# Power_Supply_for_CPU_Blocks.net
KiCad netlist of a schematic drawn in Altium Designer
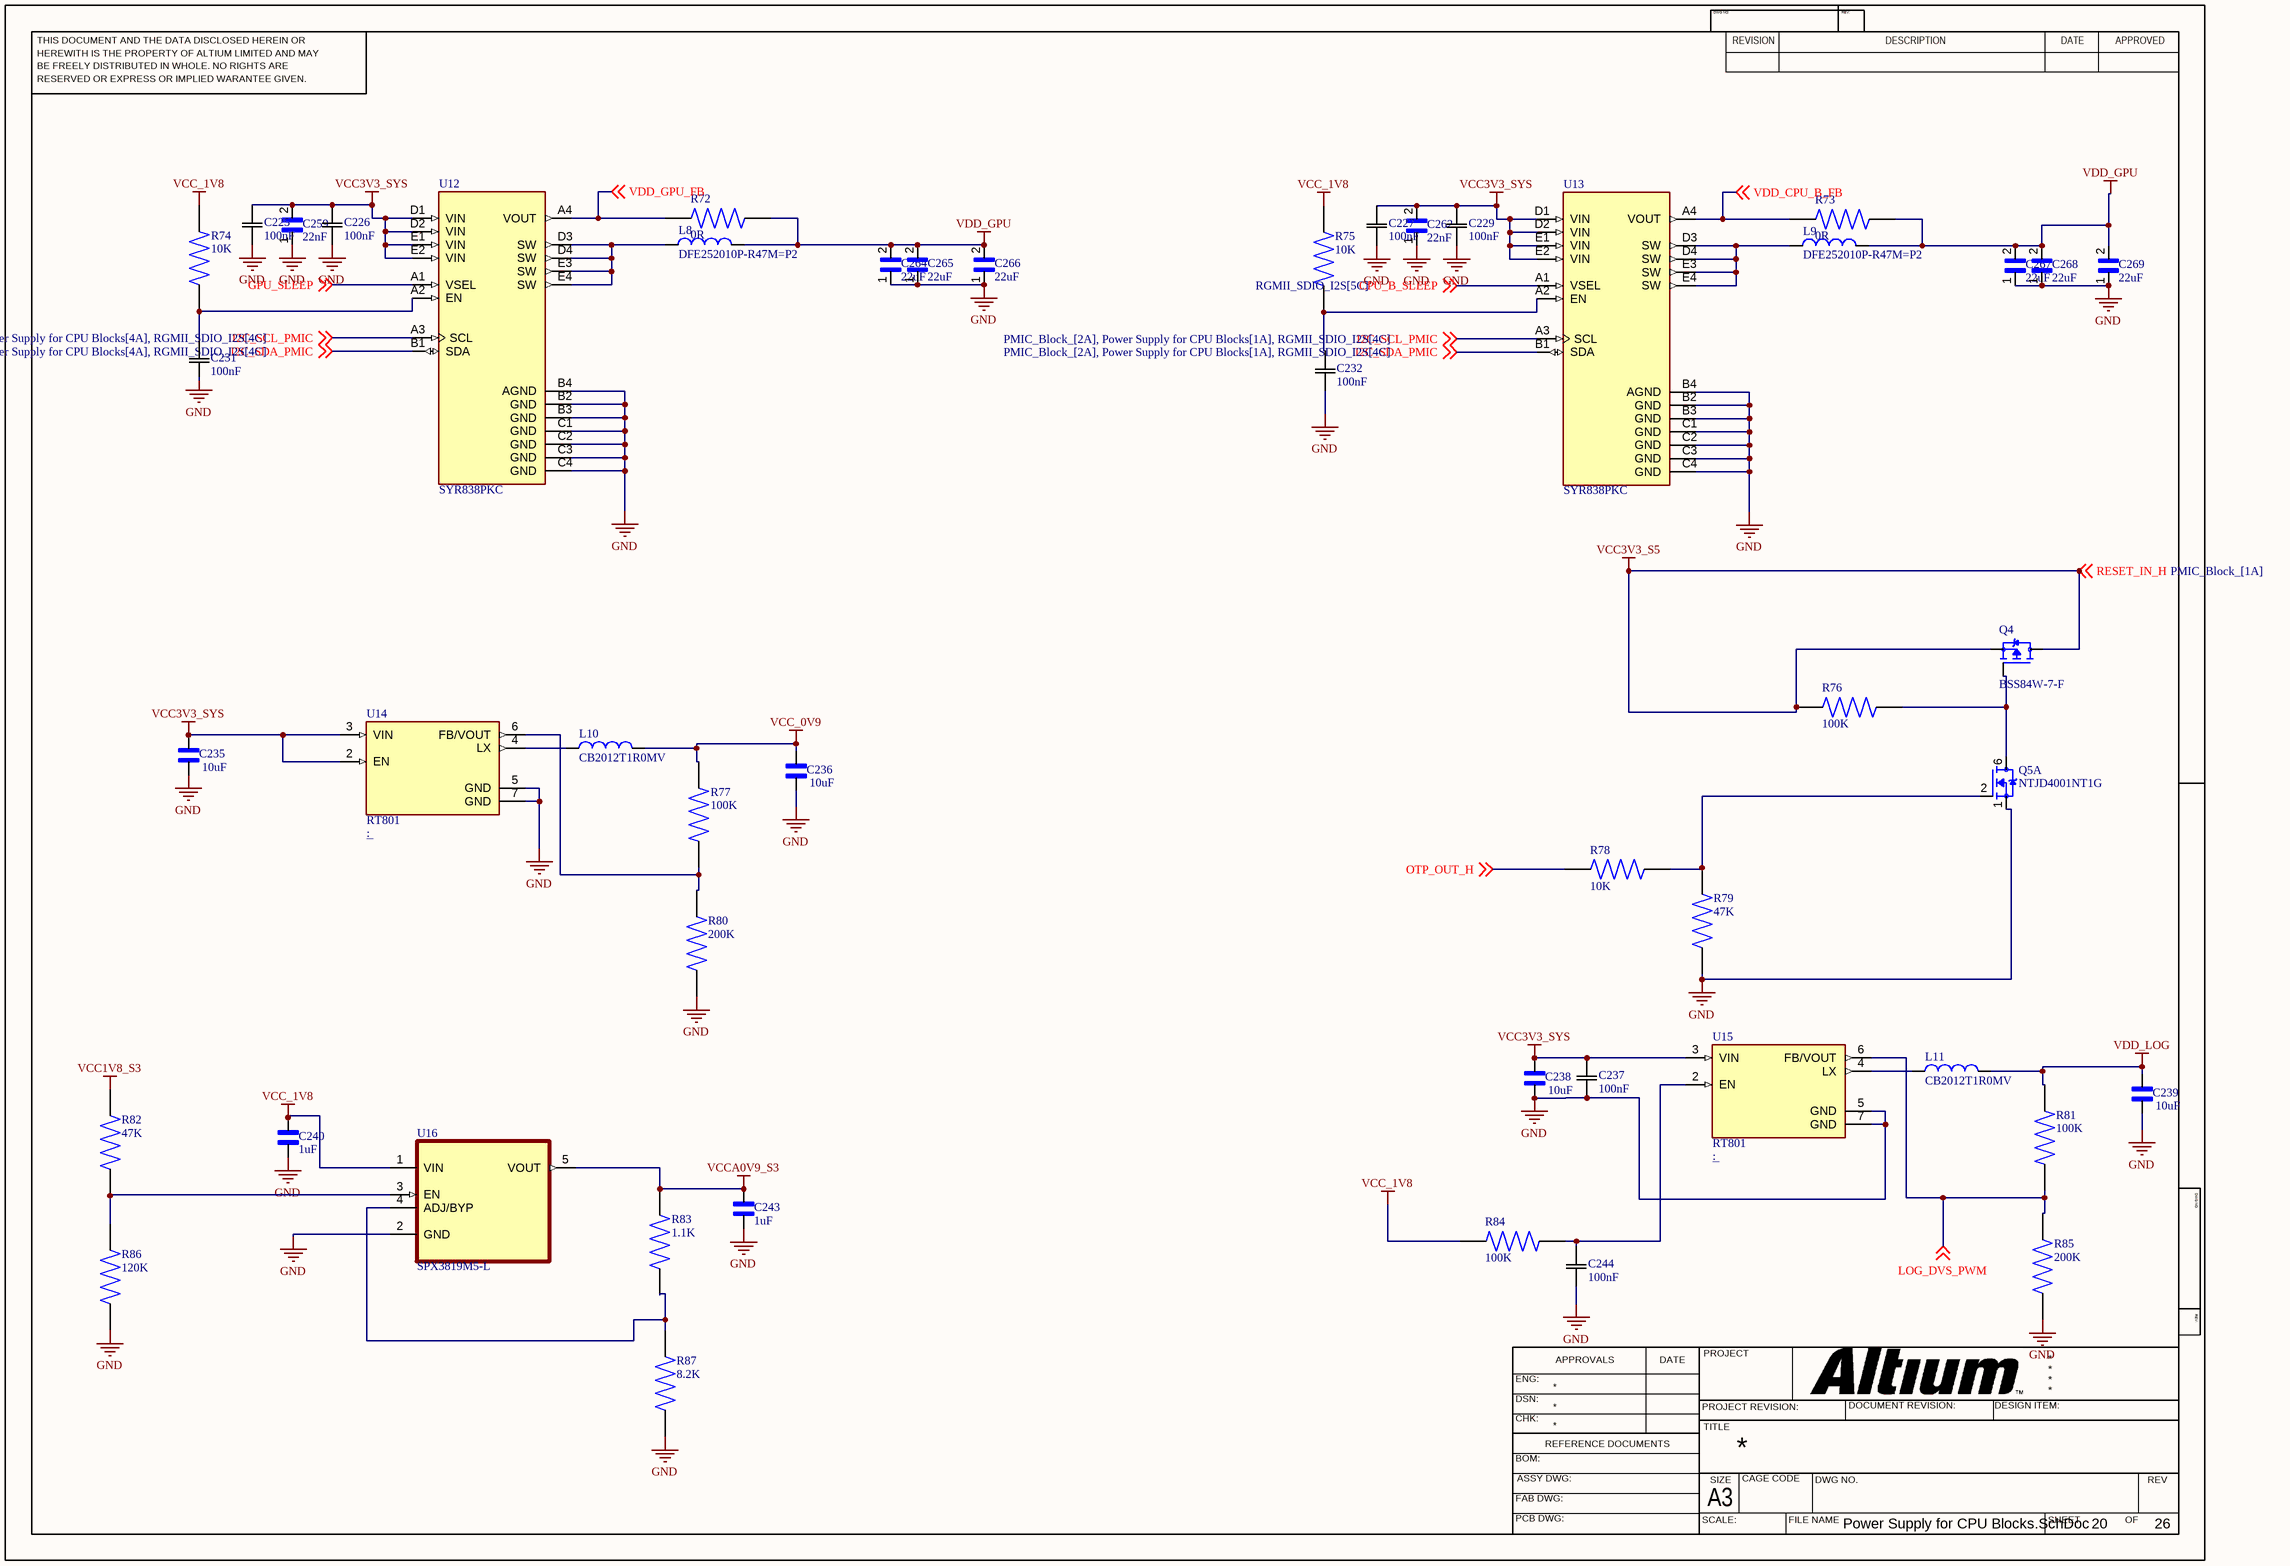
[diagram p0: Power Supply for CPU Blocks.SchDoc]

(export (version "E")
  (design (tool "Eeschema 10.0.6"))
  (components
    (comp (ref "C225")
      (value "100nF")
      (footprint "CAP_1005_TDK")
      (description "Description")
      (fields
        (field (name "MANUFACTURER_PART_NUMBER") "C1005X7R1H104M050BB")
        (field (name "COPYRIGHT") "Copyright (C) 2025 Ultra Librarian. All rights reserved.")
      )
      (libsource (lib "C1005X7R1H104M050BB") (part "C1005X7R1H104M050BB"))
    )
    (comp (ref "C226")
      (value "100nF")
      (footprint "CAP_1005_TDK")
      (description "Description")
      (fields
        (field (name "MANUFACTURER_PART_NUMBER") "C1005X7R1H104M050BB")
        (field (name "COPYRIGHT") "Copyright (C) 2025 Ultra Librarian. All rights reserved.")
      )
      (libsource (lib "C1005X7R1H104M050BB") (part "C1005X7R1H104M050BB"))
    )
    (comp (ref "C227")
      (value "100nF")
      (footprint "CAP_1005_TDK")
      (description "Description")
      (fields
        (field (name "MANUFACTURER_PART_NUMBER") "C1005X7R1H104M050BB")
        (field (name "COPYRIGHT") "Copyright (C) 2025 Ultra Librarian. All rights reserved.")
      )
      (libsource (lib "C1005X7R1H104M050BB") (part "C1005X7R1H104M050BB"))
    )
    (comp (ref "C229")
      (value "100nF")
      (footprint "CAP_1005_TDK")
      (description "Description")
      (fields
        (field (name "MANUFACTURER_PART_NUMBER") "C1005X7R1H104M050BB")
        (field (name "COPYRIGHT") "Copyright (C) 2025 Ultra Librarian. All rights reserved.")
      )
      (libsource (lib "C1005X7R1H104M050BB") (part "C1005X7R1H104M050BB"))
    )
    (comp (ref "C231")
      (value "100nF")
      (footprint "CAP_1005_TDK")
      (description "Description")
      (fields
        (field (name "MANUFACTURER_PART_NUMBER") "C1005X7R1H104M050BB")
        (field (name "COPYRIGHT") "Copyright (C) 2025 Ultra Librarian. All rights reserved.")
      )
      (libsource (lib "C1005X7R1H104M050BB") (part "C1005X7R1H104M050BB"))
    )
    (comp (ref "C232")
      (value "100nF")
      (footprint "CAP_1005_TDK")
      (description "Description")
      (fields
        (field (name "MANUFACTURER_PART_NUMBER") "C1005X7R1H104M050BB")
        (field (name "COPYRIGHT") "Copyright (C) 2025 Ultra Librarian. All rights reserved.")
      )
      (libsource (lib "C1005X7R1H104M050BB") (part "C1005X7R1H104M050BB"))
    )
    (comp (ref "C235")
      (value "10uF")
      (footprint "CAPC1005X70N")
      (description "10 ÂµF Â±20% 6.3V Ceramic Capacitor X5R 0402 (1005 Metric)")
      (fields (field (name "MF") "Samsung") (field (name "MP") "CL05A106MQ5NUNC"))
      (libsource (lib "CL05A106MQ5NUNC") (part "CL05A106MQ5NUNC"))
    )
    (comp (ref "C236")
      (value "10uF")
      (footprint "CAPC1005X70N")
      (description "10 ÂµF Â±20% 6.3V Ceramic Capacitor X5R 0402 (1005 Metric)")
      (fields (field (name "MF") "Samsung") (field (name "MP") "CL05A106MQ5NUNC"))
      (libsource (lib "CL05A106MQ5NUNC") (part "CL05A106MQ5NUNC"))
    )
    (comp (ref "C237")
      (value "100nF")
      (footprint "CAP_1005_TDK")
      (description "Description")
      (fields
        (field (name "MANUFACTURER_PART_NUMBER") "C1005X7R1H104M050BB")
        (field (name "COPYRIGHT") "Copyright (C) 2025 Ultra Librarian. All rights reserved.")
      )
      (libsource (lib "C1005X7R1H104M050BB") (part "C1005X7R1H104M050BB"))
    )
    (comp (ref "C238")
      (value "10uF")
      (footprint "CAPC1005X70N")
      (description "10 ÂµF Â±20% 6.3V Ceramic Capacitor X5R 0402 (1005 Metric)")
      (fields (field (name "MF") "Samsung") (field (name "MP") "CL05A106MQ5NUNC"))
      (libsource (lib "CL05A106MQ5NUNC") (part "CL05A106MQ5NUNC"))
    )
    (comp (ref "C239")
      (value "10uF")
      (footprint "CAPC1005X70N")
      (description "10 ÂµF Â±20% 6.3V Ceramic Capacitor X5R 0402 (1005 Metric)")
      (fields (field (name "MF") "Samsung") (field (name "MP") "CL05A106MQ5NUNC"))
      (libsource (lib "CL05A106MQ5NUNC") (part "CL05A106MQ5NUNC"))
    )
    (comp (ref "C240")
      (value "1uF")
      (footprint "CAPC1005X56N")
      (description "1 ÂµF Â±10% 10V Ceramic Capacitor X5R 0402 (1005 Metric)")
      (fields (field (name "MF") "AVX") (field (name "MP") "0402ZD105KAT4A"))
      (libsource (lib "0402ZD105KAT4A") (part "0402ZD105KAT4A"))
    )
    (comp (ref "C243")
      (value "1uF")
      (footprint "CAPC1005X56N")
      (description "1 ÂµF Â±10% 10V Ceramic Capacitor X5R 0402 (1005 Metric)")
      (fields (field (name "MF") "AVX") (field (name "MP") "0402ZD105KAT4A"))
      (libsource (lib "0402ZD105KAT4A") (part "0402ZD105KAT4A"))
    )
    (comp (ref "C244")
      (value "100nF")
      (footprint "CAP_1005_TDK")
      (description "Description")
      (fields
        (field (name "MANUFACTURER_PART_NUMBER") "C1005X7R1H104M050BB")
        (field (name "COPYRIGHT") "Copyright (C) 2025 Ultra Librarian. All rights reserved.")
      )
      (libsource (lib "C1005X7R1H104M050BB") (part "C1005X7R1H104M050BB"))
    )
    (comp (ref "C259")
      (value "22nF")
      (footprint "CAPC6050X550N")
      (description "22ÂµF Â±20% 50V Ceramic Capacitor X7S Stacked SMD, 2 J-Lead")
      (fields (field (name "MP") "CKG57NX7S1H226M500JJ"))
      (libsource (lib "CKG57NX7S1H226M500JJ") (part "CKG57NX7S1H226M500JJ"))
    )
    (comp (ref "C262")
      (value "22nF")
      (footprint "CAPC6050X550N")
      (description "22ÂµF Â±20% 50V Ceramic Capacitor X7S Stacked SMD, 2 J-Lead")
      (fields (field (name "MP") "CKG57NX7S1H226M500JJ"))
      (libsource (lib "CKG57NX7S1H226M500JJ") (part "CKG57NX7S1H226M500JJ"))
    )
    (comp (ref "C264")
      (value "22uF")
      (footprint "CAPC6050X550N")
      (description "22ÂµF Â±20% 50V Ceramic Capacitor X7S Stacked SMD, 2 J-Lead")
      (fields (field (name "MP") "CKG57NX7S1H226M500JJ"))
      (libsource (lib "CKG57NX7S1H226M500JJ") (part "CKG57NX7S1H226M500JJ"))
    )
    (comp (ref "C265")
      (value "22uF")
      (footprint "CAPC6050X550N")
      (description "22ÂµF Â±20% 50V Ceramic Capacitor X7S Stacked SMD, 2 J-Lead")
      (fields (field (name "MP") "CKG57NX7S1H226M500JJ"))
      (libsource (lib "CKG57NX7S1H226M500JJ") (part "CKG57NX7S1H226M500JJ"))
    )
    (comp (ref "C266")
      (value "22uF")
      (footprint "CAPC6050X550N")
      (description "22ÂµF Â±20% 50V Ceramic Capacitor X7S Stacked SMD, 2 J-Lead")
      (fields (field (name "MP") "CKG57NX7S1H226M500JJ"))
      (libsource (lib "CKG57NX7S1H226M500JJ") (part "CKG57NX7S1H226M500JJ"))
    )
    (comp (ref "C267")
      (value "22uF")
      (footprint "CAPC6050X550N")
      (description "22ÂµF Â±20% 50V Ceramic Capacitor X7S Stacked SMD, 2 J-Lead")
      (fields (field (name "MP") "CKG57NX7S1H226M500JJ"))
      (libsource (lib "CKG57NX7S1H226M500JJ") (part "CKG57NX7S1H226M500JJ"))
    )
    (comp (ref "C268")
      (value "22uF")
      (footprint "CAPC6050X550N")
      (description "22ÂµF Â±20% 50V Ceramic Capacitor X7S Stacked SMD, 2 J-Lead")
      (fields (field (name "MP") "CKG57NX7S1H226M500JJ"))
      (libsource (lib "CKG57NX7S1H226M500JJ") (part "CKG57NX7S1H226M500JJ"))
    )
    (comp (ref "C269")
      (value "22uF")
      (footprint "CAPC6050X550N")
      (description "22ÂµF Â±20% 50V Ceramic Capacitor X7S Stacked SMD, 2 J-Lead")
      (fields (field (name "MP") "CKG57NX7S1H226M500JJ"))
      (libsource (lib "CKG57NX7S1H226M500JJ") (part "CKG57NX7S1H226M500JJ"))
    )
    (comp (ref "L8")
      (value "DFE252010P-R47M=P2")
      (footprint "INDC2520X100N")
      (description "INDUCTOR, SHLD, 0.47UH, 20%, 4.1A, 1008")
      (libsource (lib "DFE252010P-R47M=P2") (part "DFE252010P-R47M=P2"))
    )
    (comp (ref "L9")
      (value "DFE252010P-R47M=P2")
      (footprint "INDC2520X100N")
      (description "INDUCTOR, SHLD, 0.47UH, 20%, 4.1A, 1008")
      (libsource (lib "DFE252010P-R47M=P2") (part "DFE252010P-R47M=P2"))
    )
    (comp (ref "L10")
      (value "CB2012T1R0MV")
      (footprint "INDC2012X145N")
      (description "1 ÂµH Unshielded Drum Core, Wirewound Inductor 700 mA 195mOhm Max 0805 (2012 Metric)")
      (fields (field (name "MF") "Taiyo Yuden"))
      (libsource (lib "CB2012T1R0MV") (part "CB2012T1R0MV"))
    )
    (comp (ref "L11")
      (value "CB2012T1R0MV")
      (footprint "INDC2012X145N")
      (description "1 ÂµH Unshielded Drum Core, Wirewound Inductor 700 mA 195mOhm Max 0805 (2012 Metric)")
      (fields (field (name "MF") "Taiyo Yuden"))
      (libsource (lib "CB2012T1R0MV") (part "CB2012T1R0MV"))
    )
    (comp (ref "Q4")
      (value "BSS84W-7-F")
      (footprint "SOT65P222X110-3N")
      (description "P-Channel 50 V 130mA (Ta) 200mW (Ta) Surface Mount SOT-323")
      (fields (field (name "MF") "Diodes Inc."))
      (libsource (lib "BSS84W-7-F") (part "BSS84W-7-F"))
    )
    (comp (ref "Q5")
      (value "NTJD4001NT1G")
      (footprint "SOT65P210X110-6N")
      (description "Mosfet Array 2 N-Channel (Dual) 30V 250mA 272mW Surface Mount SC-88/SC70-6/SOT-363")
      (fields (field (name "MF") "ON Semiconductor"))
      (libsource (lib "NTJD4001NT1G") (part "NTJD4001NT1G"))
    )
    (comp (ref "R72")
      (value "0R")
      (footprint "RES_ERJH6G0R00V")
      (fields (field (name "MP") "ERJH6G0R00V"))
      (libsource (lib "ERJH6G0R00V") (part "ERJH6G0R00V"))
    )
    (comp (ref "R73")
      (value "0R")
      (footprint "RES_ERJH6G0R00V")
      (fields (field (name "MP") "ERJH6G0R00V"))
      (libsource (lib "ERJH6G0R00V") (part "ERJH6G0R00V"))
    )
    (comp (ref "R74")
      (value "10K")
      (footprint "RES_ERA3ARB103V")
      (fields (field (name "MP") "ERA3ARB103V"))
      (libsource (lib "ERA3ARB103V") (part "ERA3ARB103V"))
    )
    (comp (ref "R75")
      (value "10K")
      (footprint "RES_ERA3ARB103V")
      (fields (field (name "MP") "ERA3ARB103V"))
      (libsource (lib "ERA3ARB103V") (part "ERA3ARB103V"))
    )
    (comp (ref "R76")
      (value "100K")
      (footprint "RES_ERA3ARB103V")
      (fields (field (name "MP") "ERA3ARB103V"))
      (libsource (lib "ERA3ARB103V") (part "ERA3ARB103V"))
    )
    (comp (ref "R77")
      (value "100K")
      (footprint "RES_ERA3ARB103V")
      (fields (field (name "MP") "ERA3ARB103V"))
      (libsource (lib "ERA3ARB103V") (part "ERA3ARB103V"))
    )
    (comp (ref "R78")
      (value "10K")
      (footprint "RES_ERA3ARB103V")
      (fields (field (name "MP") "ERA3ARB103V"))
      (libsource (lib "ERA3ARB103V") (part "ERA3ARB103V"))
    )
    (comp (ref "R79")
      (value "47K")
      (footprint "RES_ERA2ARC473X")
      (fields (field (name "MP") "ERA2ARC473X"))
      (libsource (lib "ERA2ARC473X") (part "ERA2ARC473X"))
    )
    (comp (ref "R80")
      (value "200K")
      (footprint "RES_ERJP06D2003V")
      (fields (field (name "MP") "ERJP06D2003V"))
      (libsource (lib "ERJP06D2003V") (part "ERJP06D2003V"))
    )
    (comp (ref "R81")
      (value "100K")
      (footprint "RES_ERA3ARB103V")
      (fields (field (name "MP") "ERA3ARB103V"))
      (libsource (lib "ERA3ARB103V") (part "ERA3ARB103V"))
    )
    (comp (ref "R82")
      (value "47K")
      (footprint "RES_ERA2ARC473X")
      (fields (field (name "MP") "ERA2ARC473X"))
      (libsource (lib "ERA2ARC473X") (part "ERA2ARC473X"))
    )
    (comp (ref "R83")
      (value "1.1K")
      (footprint "RESC1608X50N")
      (fields (field (name "MP") "ERJP08F1101V"))
      (libsource (lib "ERJP08F1101V") (part "ERJP08F1101V"))
    )
    (comp (ref "R84")
      (value "100K")
      (footprint "RES_ERA3ARB103V")
      (fields (field (name "MP") "ERA3ARB103V"))
      (libsource (lib "ERA3ARB103V") (part "ERA3ARB103V"))
    )
    (comp (ref "R85")
      (value "200K")
      (footprint "RES_ERJP06D2003V")
      (fields (field (name "MP") "ERJP06D2003V"))
      (libsource (lib "ERJP06D2003V") (part "ERJP06D2003V"))
    )
    (comp (ref "R86")
      (value "120K")
      (footprint "RES_ERA8AEB124V")
      (fields (field (name "MP") "ERA8AEB124V"))
      (libsource (lib "ERA8AEB124V") (part "ERA8AEB124V"))
    )
    (comp (ref "R87")
      (value "8.2K")
      (footprint "RES_ERA2APB822X")
      (fields (field (name "MP") "ERA2APB822X"))
      (libsource (lib "ERA2APB822X") (part "ERA2APB822X"))
    )
    (comp (ref "U12")
      (value "SYR838PKC")
      (footprint "BGA20N40P5X4_196X156X66N")
      (fields (field (name "MF") "Silergy"))
      (libsource (lib "SYR838PKC") (part "SYR838PKC"))
    )
    (comp (ref "U13")
      (value "SYR838PKC")
      (footprint "BGA20N40P5X4_196X156X66N")
      (fields (field (name "MF") "Silergy"))
      (libsource (lib "SYR838PKC") (part "SYR838PKC"))
    )
    (comp (ref "U14")
      (value "RT801")
      (footprint "SON65P200X200X80-7N")
      (description "Buck Switching Regulator IC Positive Adjustable 0.6V 1 Output 1A 6-WDFN Exposed Pad")
      (fields (field (name "MP") "RT8010GQW") (field (name "MF") "Richtek USA"))
      (libsource (lib "RT8010GQW") (part "RT8010GQW"))
    )
    (comp (ref "U15")
      (value "RT801")
      (footprint "SON65P200X200X80-7N")
      (description "Buck Switching Regulator IC Positive Adjustable 0.6V 1 Output 1A 6-WDFN Exposed Pad")
      (fields (field (name "MP") "RT8010GQW") (field (name "MF") "Richtek USA"))
      (libsource (lib "RT8010GQW") (part "RT8010GQW"))
    )
    (comp (ref "U16")
      (value "SPX3819M5-L")
      (footprint "SOT95P280X145-5N")
      (description "Linear Voltage Regulator IC Positive Adjustable 1 Output 500mA SOT-23-5")
      (fields (field (name "MF") "MaxLinear, Inc.") (field (name "MP") "SPX3819M5-L/TR"))
      (libsource (lib "SPX3819M5-L") (part "SPX3819M5-L"))
    )
  )
  (nets
    (net (code "1") (name "CPU_B_SLEEP") (class "Default")
      (node (ref "U13") (pin "A1") (pinfunction "VSEL_A1") (pintype "input"))
    )
    (net (code "2") (name "GND") (class "Default")
      (node (ref "C225") (pin "1") (pinfunction "1_1") (pintype "passive"))
      (node (ref "C226") (pin "1") (pinfunction "1_1") (pintype "passive"))
      (node (ref "C227") (pin "1") (pinfunction "1_1") (pintype "passive"))
      (node (ref "C229") (pin "1") (pinfunction "1_1") (pintype "passive"))
      (node (ref "C231") (pin "1") (pinfunction "1_1") (pintype "passive"))
      (node (ref "C232") (pin "1") (pinfunction "1_1") (pintype "passive"))
      (node (ref "C235") (pin "1") (pinfunction "1_1") (pintype "passive"))
      (node (ref "C236") (pin "1") (pinfunction "1_1") (pintype "passive"))
      (node (ref "C237") (pin "1") (pinfunction "1_1") (pintype "passive"))
      (node (ref "C238") (pin "1") (pinfunction "1_1") (pintype "passive"))
      (node (ref "C239") (pin "1") (pinfunction "1_1") (pintype "passive"))
      (node (ref "C240") (pin "1") (pinfunction "1_1") (pintype "passive"))
      (node (ref "C243") (pin "1") (pinfunction "1_1") (pintype "passive"))
      (node (ref "C244") (pin "1") (pinfunction "1_1") (pintype "passive"))
      (node (ref "C259") (pin "1") (pinfunction "1_1") (pintype "passive"))
      (node (ref "C262") (pin "1") (pinfunction "1_1") (pintype "passive"))
      (node (ref "C264") (pin "1") (pinfunction "1_1") (pintype "passive"))
      (node (ref "C265") (pin "1") (pinfunction "1_1") (pintype "passive"))
      (node (ref "C266") (pin "1") (pinfunction "1_1") (pintype "passive"))
      (node (ref "C267") (pin "1") (pinfunction "1_1") (pintype "passive"))
      (node (ref "C268") (pin "1") (pinfunction "1_1") (pintype "passive"))
      (node (ref "C269") (pin "1") (pinfunction "1_1") (pintype "passive"))
      (node (ref "Q5") (pin "1") (pinfunction "S1_1") (pintype "passive"))
      (node (ref "R79") (pin "1") (pinfunction "1_1") (pintype "passive"))
      (node (ref "R80") (pin "1") (pinfunction "1_1") (pintype "passive"))
      (node (ref "R85") (pin "1") (pinfunction "1_1") (pintype "passive"))
      (node (ref "R86") (pin "1") (pinfunction "1_1") (pintype "passive"))
      (node (ref "R87") (pin "1") (pinfunction "1_1") (pintype "passive"))
      (node (ref "U12") (pin "B2") (pinfunction "GND_B2") (pintype "power_in"))
      (node (ref "U12") (pin "B3") (pinfunction "GND_B3") (pintype "power_in"))
      (node (ref "U12") (pin "B4") (pinfunction "AGND_B4") (pintype "power_in"))
      (node (ref "U12") (pin "C1") (pinfunction "GND_C1") (pintype "power_in"))
      (node (ref "U12") (pin "C2") (pinfunction "GND_C2") (pintype "power_in"))
      (node (ref "U12") (pin "C3") (pinfunction "GND_C3") (pintype "power_in"))
      (node (ref "U12") (pin "C4") (pinfunction "GND_C4") (pintype "power_in"))
      (node (ref "U13") (pin "B2") (pinfunction "GND_B2") (pintype "power_in"))
      (node (ref "U13") (pin "B3") (pinfunction "GND_B3") (pintype "power_in"))
      (node (ref "U13") (pin "B4") (pinfunction "AGND_B4") (pintype "power_in"))
      (node (ref "U13") (pin "C1") (pinfunction "GND_C1") (pintype "power_in"))
      (node (ref "U13") (pin "C2") (pinfunction "GND_C2") (pintype "power_in"))
      (node (ref "U13") (pin "C3") (pinfunction "GND_C3") (pintype "power_in"))
      (node (ref "U13") (pin "C4") (pinfunction "GND_C4") (pintype "power_in"))
      (node (ref "U14") (pin "5") (pinfunction "GND_5") (pintype "power_in"))
      (node (ref "U14") (pin "7") (pinfunction "GND_7") (pintype "power_in"))
      (node (ref "U15") (pin "5") (pinfunction "GND_5") (pintype "power_in"))
      (node (ref "U15") (pin "7") (pinfunction "GND_7") (pintype "power_in"))
      (node (ref "U16") (pin "2") (pinfunction "GND_2") (pintype "passive"))
    )
    (net (code "3") (name "GPU_SLEEP") (class "Default")
      (node (ref "U12") (pin "A1") (pinfunction "VSEL_A1") (pintype "input"))
    )
    (net (code "4") (name "I2C_SCL_PMIC") (class "Default")
      (node (ref "U12") (pin "A3") (pinfunction "SCL_A3") (pintype "input"))
      (node (ref "U13") (pin "A3") (pinfunction "SCL_A3") (pintype "input"))
    )
    (net (code "5") (name "I2C_SDA_PMIC") (class "Default")
      (node (ref "U12") (pin "B1") (pinfunction "SDA_B1") (pintype "bidirectional"))
      (node (ref "U13") (pin "B1") (pinfunction "SDA_B1") (pintype "bidirectional"))
    )
    (net (code "6") (name "LOG_DVS_PWM") (class "Default")
      (node (ref "R81") (pin "1") (pinfunction "1_1") (pintype "passive"))
      (node (ref "R85") (pin "2") (pinfunction "2_2") (pintype "passive"))
      (node (ref "U15") (pin "6") (pinfunction "FB/VOUT_6") (pintype "output"))
    )
    (net (code "7") (name "Net-(L8-Pad1)") (class "Default")
      (node (ref "L8") (pin "1") (pinfunction "1_1") (pintype "passive"))
      (node (ref "U12") (pin "D3") (pinfunction "SW_D3") (pintype "output"))
      (node (ref "U12") (pin "D4") (pinfunction "SW_D4") (pintype "output"))
      (node (ref "U12") (pin "E3") (pinfunction "SW_E3") (pintype "output"))
      (node (ref "U12") (pin "E4") (pinfunction "SW_E4") (pintype "output"))
    )
    (net (code "8") (name "Net-(L9-Pad1)") (class "Default")
      (node (ref "L9") (pin "1") (pinfunction "1_1") (pintype "passive"))
      (node (ref "U13") (pin "D3") (pinfunction "SW_D3") (pintype "output"))
      (node (ref "U13") (pin "D4") (pinfunction "SW_D4") (pintype "output"))
      (node (ref "U13") (pin "E3") (pinfunction "SW_E3") (pintype "output"))
      (node (ref "U13") (pin "E4") (pinfunction "SW_E4") (pintype "output"))
    )
    (net (code "9") (name "Net-(Q4-G)") (class "Default")
      (node (ref "Q4") (pin "1") (pinfunction "G_1") (pintype "passive"))
      (node (ref "Q5") (pin "6") (pinfunction "D1_6") (pintype "passive"))
      (node (ref "R76") (pin "1") (pinfunction "1_1") (pintype "passive"))
    )
    (net (code "10") (name "Net-(Q5A-G1)") (class "Default")
      (node (ref "Q5") (pin "2") (pinfunction "G1_2") (pintype "passive"))
      (node (ref "R78") (pin "1") (pinfunction "1_1") (pintype "passive"))
      (node (ref "R79") (pin "2") (pinfunction "2_2") (pintype "passive"))
    )
    (net (code "11") (name "Net-(U12-EN)") (class "Default")
      (node (ref "C231") (pin "2") (pinfunction "2_2") (pintype "passive"))
      (node (ref "R74") (pin "1") (pinfunction "1_1") (pintype "passive"))
      (node (ref "U12") (pin "A2") (pinfunction "EN_A2") (pintype "input"))
    )
    (net (code "12") (name "Net-(U13-EN)") (class "Default")
      (node (ref "C232") (pin "2") (pinfunction "2_2") (pintype "passive"))
      (node (ref "R75") (pin "1") (pinfunction "1_1") (pintype "passive"))
      (node (ref "U13") (pin "A2") (pinfunction "EN_A2") (pintype "input"))
    )
    (net (code "13") (name "Net-(U14-FB{slash}VOUT)") (class "Default")
      (node (ref "R77") (pin "1") (pinfunction "1_1") (pintype "passive"))
      (node (ref "R80") (pin "2") (pinfunction "2_2") (pintype "passive"))
      (node (ref "U14") (pin "6") (pinfunction "FB/VOUT_6") (pintype "output"))
    )
    (net (code "14") (name "Net-(U14-LX)") (class "Default")
      (node (ref "L10") (pin "1") (pinfunction "1_1") (pintype "passive"))
      (node (ref "U14") (pin "4") (pinfunction "LX_4") (pintype "output"))
    )
    (net (code "15") (name "Net-(U15-EN)") (class "Default")
      (node (ref "C244") (pin "2") (pinfunction "2_2") (pintype "passive"))
      (node (ref "R84") (pin "1") (pinfunction "1_1") (pintype "passive"))
      (node (ref "U15") (pin "2") (pinfunction "EN_2") (pintype "input"))
    )
    (net (code "16") (name "Net-(U15-LX)") (class "Default")
      (node (ref "L11") (pin "1") (pinfunction "1_1") (pintype "passive"))
      (node (ref "U15") (pin "4") (pinfunction "LX_4") (pintype "output"))
    )
    (net (code "17") (name "Net-(U16-ADJ{slash}BYP)") (class "Default")
      (node (ref "R83") (pin "1") (pinfunction "1_1") (pintype "passive"))
      (node (ref "R87") (pin "2") (pinfunction "2_2") (pintype "passive"))
      (node (ref "U16") (pin "4") (pinfunction "ADJ/BYP_4") (pintype "passive"))
    )
    (net (code "18") (name "Net-(U16-EN)") (class "Default")
      (node (ref "R82") (pin "1") (pinfunction "1_1") (pintype "passive"))
      (node (ref "R86") (pin "2") (pinfunction "2_2") (pintype "passive"))
      (node (ref "U16") (pin "3") (pinfunction "EN_3") (pintype "input"))
    )
    (net (code "19") (name "OTP_OUT_H") (class "Default")
      (node (ref "R78") (pin "2") (pinfunction "2_2") (pintype "passive"))
    )
    (net (code "20") (name "RESET_IN_H") (class "Default")
      (node (ref "Q4") (pin "2") (pinfunction "S_2") (pintype "passive"))
      (node (ref "Q4") (pin "3") (pinfunction "D_3") (pintype "passive"))
      (node (ref "R76") (pin "2") (pinfunction "2_2") (pintype "passive"))
    )
    (net (code "21") (name "VCC1V8_S3") (class "Default")
      (node (ref "R82") (pin "2") (pinfunction "2_2") (pintype "passive"))
    )
    (net (code "22") (name "VCC3V3_SYS") (class "Default")
      (node (ref "C225") (pin "2") (pinfunction "2_2") (pintype "passive"))
      (node (ref "C226") (pin "2") (pinfunction "2_2") (pintype "passive"))
      (node (ref "C227") (pin "2") (pinfunction "2_2") (pintype "passive"))
      (node (ref "C229") (pin "2") (pinfunction "2_2") (pintype "passive"))
      (node (ref "C235") (pin "2") (pinfunction "2_2") (pintype "passive"))
      (node (ref "C237") (pin "2") (pinfunction "2_2") (pintype "passive"))
      (node (ref "C238") (pin "2") (pinfunction "2_2") (pintype "passive"))
      (node (ref "C259") (pin "2") (pinfunction "2_2") (pintype "passive"))
      (node (ref "C262") (pin "2") (pinfunction "2_2") (pintype "passive"))
      (node (ref "U12") (pin "D1") (pinfunction "VIN_D1") (pintype "input"))
      (node (ref "U12") (pin "D2") (pinfunction "VIN_D2") (pintype "input"))
      (node (ref "U12") (pin "E1") (pinfunction "VIN_E1") (pintype "input"))
      (node (ref "U12") (pin "E2") (pinfunction "VIN_E2") (pintype "input"))
      (node (ref "U13") (pin "D1") (pinfunction "VIN_D1") (pintype "input"))
      (node (ref "U13") (pin "D2") (pinfunction "VIN_D2") (pintype "input"))
      (node (ref "U13") (pin "E1") (pinfunction "VIN_E1") (pintype "input"))
      (node (ref "U13") (pin "E2") (pinfunction "VIN_E2") (pintype "input"))
      (node (ref "U14") (pin "2") (pinfunction "EN_2") (pintype "input"))
      (node (ref "U14") (pin "3") (pinfunction "VIN_3") (pintype "input"))
      (node (ref "U15") (pin "3") (pinfunction "VIN_3") (pintype "input"))
    )
    (net (code "23") (name "VCCA0V9_S3") (class "Default")
      (node (ref "C243") (pin "2") (pinfunction "2_2") (pintype "passive"))
      (node (ref "R83") (pin "2") (pinfunction "2_2") (pintype "passive"))
      (node (ref "U16") (pin "5") (pinfunction "VOUT_5") (pintype "output"))
    )
    (net (code "24") (name "VCC_0V9") (class "Default")
      (node (ref "C236") (pin "2") (pinfunction "2_2") (pintype "passive"))
      (node (ref "L10") (pin "2") (pinfunction "2_2") (pintype "passive"))
      (node (ref "R77") (pin "2") (pinfunction "2_2") (pintype "passive"))
    )
    (net (code "25") (name "VCC_1V8") (class "Default")
      (node (ref "C240") (pin "2") (pinfunction "2_2") (pintype "passive"))
      (node (ref "R74") (pin "2") (pinfunction "2_2") (pintype "passive"))
      (node (ref "R75") (pin "2") (pinfunction "2_2") (pintype "passive"))
      (node (ref "R84") (pin "2") (pinfunction "2_2") (pintype "passive"))
      (node (ref "U16") (pin "1") (pinfunction "VIN_1") (pintype "power_in"))
    )
    (net (code "26") (name "VDD_CPU_B_FB") (class "Default")
      (node (ref "R73") (pin "1") (pinfunction "1_1") (pintype "passive"))
      (node (ref "U13") (pin "A4") (pinfunction "VOUT_A4") (pintype "output"))
    )
    (net (code "27") (name "VDD_GPU") (class "Default")
      (node (ref "C264") (pin "2") (pinfunction "2_2") (pintype "passive"))
      (node (ref "C265") (pin "2") (pinfunction "2_2") (pintype "passive"))
      (node (ref "C266") (pin "2") (pinfunction "2_2") (pintype "passive"))
      (node (ref "C267") (pin "2") (pinfunction "2_2") (pintype "passive"))
      (node (ref "C268") (pin "2") (pinfunction "2_2") (pintype "passive"))
      (node (ref "C269") (pin "2") (pinfunction "2_2") (pintype "passive"))
      (node (ref "L8") (pin "2") (pinfunction "2_2") (pintype "passive"))
      (node (ref "L9") (pin "2") (pinfunction "2_2") (pintype "passive"))
      (node (ref "R72") (pin "2") (pinfunction "2_2") (pintype "passive"))
      (node (ref "R73") (pin "2") (pinfunction "2_2") (pintype "passive"))
    )
    (net (code "28") (name "VDD_GPU_FB") (class "Default")
      (node (ref "R72") (pin "1") (pinfunction "1_1") (pintype "passive"))
      (node (ref "U12") (pin "A4") (pinfunction "VOUT_A4") (pintype "output"))
    )
    (net (code "29") (name "VDD_LOG") (class "Default")
      (node (ref "C239") (pin "2") (pinfunction "2_2") (pintype "passive"))
      (node (ref "L11") (pin "2") (pinfunction "2_2") (pintype "passive"))
      (node (ref "R81") (pin "2") (pinfunction "2_2") (pintype "passive"))
    )
  )
)
